# 3_CAN.net
KiCad netlist of a schematic drawn in Altium Designer
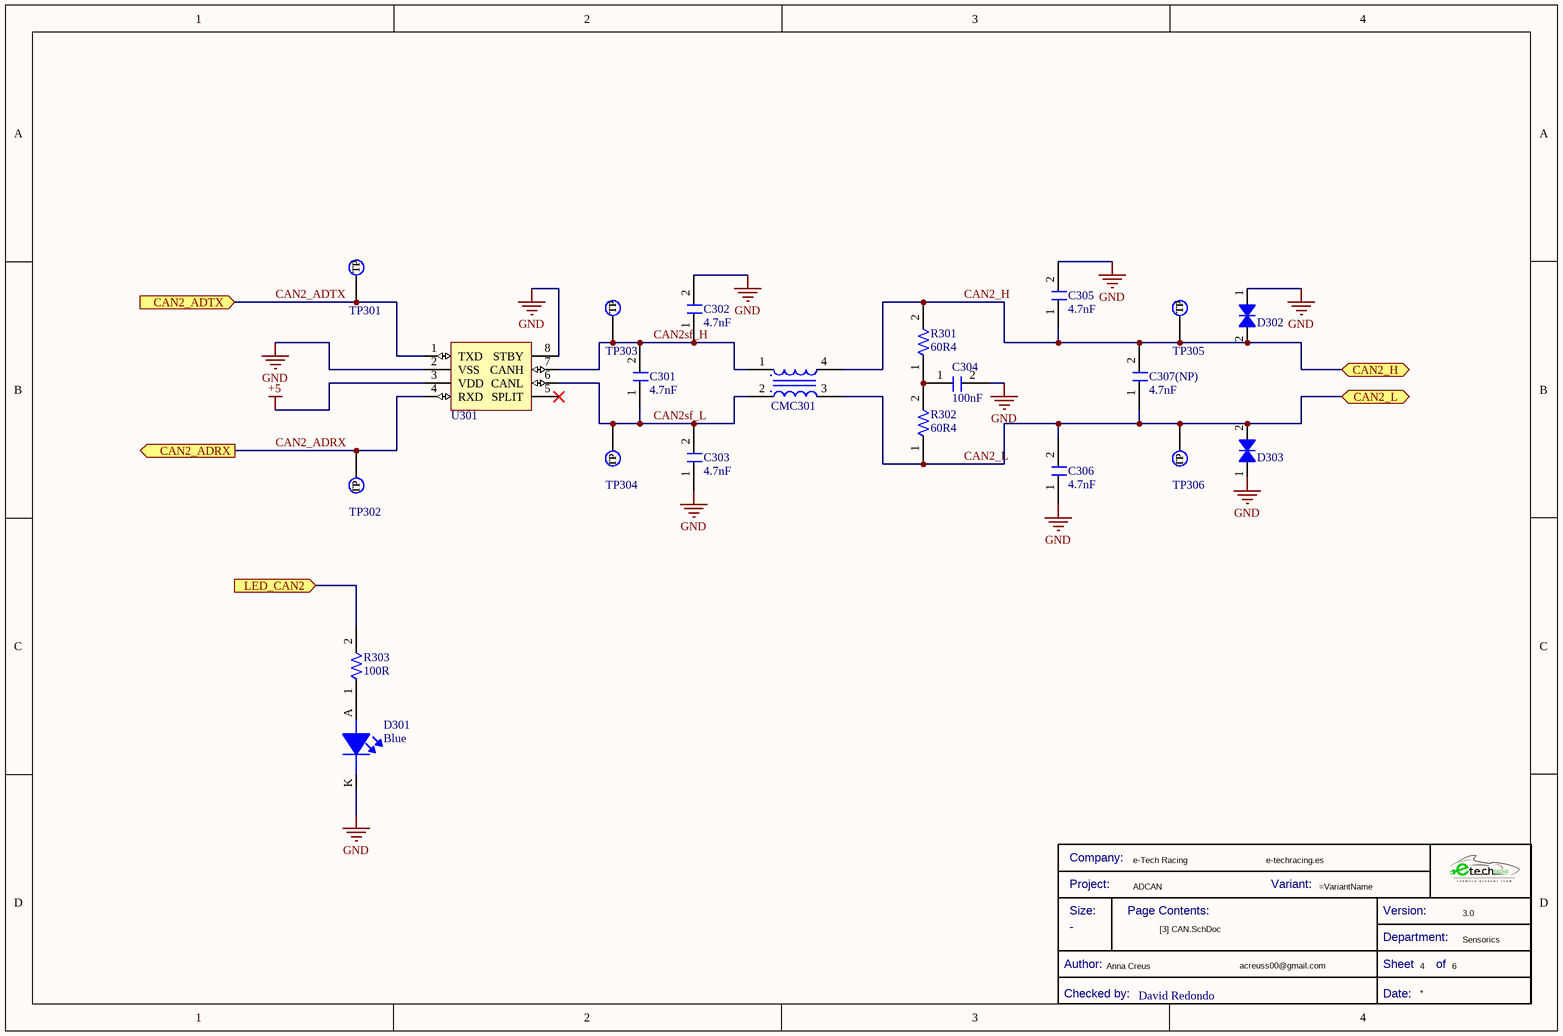
[diagram p0: [3] CAN.SchDoc]

(export (version "E")
  (design (tool "Eeschema 10.0.6"))
  (components
    (comp (ref "C301")
      (value "885012208025")
      (footprint "C1206FNPC-RW")
      (description "Cap, 4700PF, 16V, 10%, X7R, 1206")
      (fields
        (field (name "MANUFACTURER") "Wurth Electronics")
        (field (name "TOLERANCE") "10%")
        (field (name "CAPACITANCE") "4.7nF")
      )
      (libsource (lib "Passives") (part "C4.7n-16V-1206FNPC-X7R"))
    )
    (comp (ref "C302")
      (value "885012208025")
      (footprint "C1206FNPC-RW")
      (description "Cap, 4700PF, 16V, 10%, X7R, 1206")
      (fields
        (field (name "MANUFACTURER") "Wurth Electronics")
        (field (name "TOLERANCE") "10%")
        (field (name "CAPACITANCE") "4.7nF")
      )
      (libsource (lib "Passives") (part "C4.7n-16V-1206FNPC-X7R"))
    )
    (comp (ref "C303")
      (value "885012208025")
      (footprint "C1206FNPC-RW")
      (description "Cap, 4700PF, 16V, 10%, X7R, 1206")
      (fields
        (field (name "MANUFACTURER") "Wurth Electronics")
        (field (name "TOLERANCE") "10%")
        (field (name "CAPACITANCE") "4.7nF")
      )
      (libsource (lib "Passives") (part "C4.7n-16V-1206FNPC-X7R"))
    )
    (comp (ref "C304")
      (value "885012208009")
      (footprint "C1206FNPC-RW")
      (description "Cap, 0.1ΜF, 10V, 10%, X7R, 1206")
      (fields (field (name "TOLERANCE") "10%") (field (name "CAPACITANCE") "100nF"))
      (libsource (lib "Passives") (part "C100n-10V-1206FNPC-X7R"))
    )
    (comp (ref "C305")
      (value "885012208025")
      (footprint "C1206FNPC-RW")
      (description "Cap, 4700PF, 16V, 10%, X7R, 1206")
      (fields
        (field (name "MANUFACTURER") "Wurth Electronics")
        (field (name "TOLERANCE") "10%")
        (field (name "CAPACITANCE") "4.7nF")
      )
      (libsource (lib "Passives") (part "C4.7n-16V-1206FNPC-X7R"))
    )
    (comp (ref "C306")
      (value "885012208025")
      (footprint "C1206FNPC-RW")
      (description "Cap, 4700PF, 16V, 10%, X7R, 1206")
      (fields
        (field (name "MANUFACTURER") "Wurth Electronics")
        (field (name "TOLERANCE") "10%")
        (field (name "CAPACITANCE") "4.7nF")
      )
      (libsource (lib "Passives") (part "C4.7n-16V-1206FNPC-X7R"))
    )
    (comp (ref "C307(NP)")
      (value "885012208025")
      (footprint "C1206FNPC-RW")
      (description "Cap, 4700PF, 16V, 10%, X7R, 1206")
      (fields
        (field (name "MANUFACTURER") "Wurth Electronics")
        (field (name "TOLERANCE") "10%")
        (field (name "CAPACITANCE") "4.7nF")
      )
      (libsource (lib "Passives") (part "C4.7n-16V-1206FNPC-X7R"))
    )
    (comp (ref "CMC301")
      (value "744226")
      (footprint "CMC_10u_1.6A")
      (description "Common Mode Chokes Dual 10uH 920Ohm 1kHz 1.6A 80mOhm DCR SMD T/R")
      (fields (field (name "MANUFACTURER") "Wurth Electronics") (field (name "TOLERANCE") "30%"))
      (libsource (lib "Filter components") (part "CMC_10u_1.6A"))
    )
    (comp (ref "D301")
      (value "150120BS75000")
      (footprint "LED_1206_WE")
      (description "Led, Blue, 470 Nm, 3.2 V, 30 Ma, 145 Mcd Rohs Compliant: Yes")
      (fields (field (name "MANUFACTURER") "Wurth Electronics") (field (name "COLOR") "Blue"))
      (libsource (lib "Semiconductor") (part "LEDBS-1206-145"))
    )
    (comp (ref "D302")
      (value "824501600")
      (footprint "DTVS-DO-214AC")
      (description "TVS diode [Würth Elektronik] 824501600 TVS diode")
      (fields (field (name "MANUFACTURER") "Wurth Electronics"))
      (libsource (lib "Filter components") (part "DTVS-6V-DO-214AC"))
    )
    (comp (ref "D303")
      (value "824501600")
      (footprint "DTVS-DO-214AC")
      (description "TVS diode [Würth Elektronik] 824501600 TVS diode")
      (fields (field (name "MANUFACTURER") "Wurth Electronics"))
      (libsource (lib "Filter components") (part "DTVS-6V-DO-214AC"))
    )
    (comp (ref "R301")
      (value "60R4")
      (footprint "R1206FTK-W")
      (description "Res Precision Thin Film 60.4Ohm 0.1% 400mW 10ppm/°C 2-Pin 1206 SMD T/R")
      (fields
        (field (name "MANUFACTURER") "TE Connectivity Holsworthy")
        (field (name "MANUFACTURER PART NUMBER") "RQ73C2B60R4BTDF")
      )
      (libsource (lib "Passives") (part "R60-1206FTN"))
    )
    (comp (ref "R302")
      (value "60R4")
      (footprint "R1206FTK-W")
      (description "Res Precision Thin Film 60.4Ohm 0.1% 400mW 10ppm/°C 2-Pin 1206 SMD T/R")
      (fields
        (field (name "MANUFACTURER") "TE Connectivity Holsworthy")
        (field (name "MANUFACTURER PART NUMBER") "RQ73C2B60R4BTDF")
      )
      (libsource (lib "Passives") (part "R60-1206FTN"))
    )
    (comp (ref "R303")
      (value "CRG1206F100R")
      (footprint "R1206FTK-W")
      (description "Res Thick Film 1206 100 Ohm 1% 0.25W(1/4W) ±200ppm/C Pad SMD T/R")
      (fields
        (field (name "MANUFACTURER") "TE Connectivity")
        (field (name "TOLERANCE") "1%")
        (field (name "RESISTANCE") "100R")
      )
      (libsource (lib "Passives") (part "R100-1206FTK"))
    )
    (comp (ref "TP301")
      (value "TestPoint")
      (footprint "TestPoint")
      (description "Test Point 1x1 mm")
      (libsource (lib "e-Tech_Racing") (part "TestPoint"))
    )
    (comp (ref "TP302")
      (value "TestPoint")
      (footprint "TestPoint")
      (description "Test Point 1x1 mm")
      (libsource (lib "e-Tech_Racing") (part "TestPoint"))
    )
    (comp (ref "TP303")
      (value "TestPoint")
      (footprint "TestPoint")
      (description "Test Point 1x1 mm")
      (libsource (lib "e-Tech_Racing") (part "TestPoint"))
    )
    (comp (ref "TP304")
      (value "TestPoint")
      (footprint "TestPoint")
      (description "Test Point 1x1 mm")
      (libsource (lib "e-Tech_Racing") (part "TestPoint"))
    )
    (comp (ref "TP305")
      (value "TestPoint")
      (footprint "TestPoint")
      (description "Test Point 1x1 mm")
      (libsource (lib "e-Tech_Racing") (part "TestPoint"))
    )
    (comp (ref "TP306")
      (value "TestPoint")
      (footprint "TestPoint")
      (description "Test Point 1x1 mm")
      (libsource (lib "e-Tech_Racing") (part "TestPoint"))
    )
    (comp (ref "U301")
      (value "MCP2561-H/SN")
      (footprint "Transceiver_CAN")
      (description "CAN Transceiver, 4.5 to 5.5V, 70mA, -40 to 150C, SOIC-8, RoHS")
      (fields (field (name "MANUFACTURER") "Digi-Key") (field (name "MANUFACTURER PART") "Microchip"))
      (libsource (lib "Integrated circuits") (part "Transceiver_CAN"))
    )
  )
  (nets
    (net (code "1") (name "+5") (class "Default")
      (node (ref "U301") (pin "3") (pinfunction "VDD_3") (pintype "power_in"))
    )
    (net (code "2") (name "/CAN2_ADRX") (class "Default")
      (node (ref "TP302") (pin "1") (pinfunction "TP_1") (pintype "passive"))
      (node (ref "U301") (pin "4") (pinfunction "RXD_4") (pintype "bidirectional"))
    )
    (net (code "3") (name "/CAN2_ADTX") (class "Default")
      (node (ref "TP301") (pin "1") (pinfunction "TP_1") (pintype "passive"))
      (node (ref "U301") (pin "1") (pinfunction "TXD_1") (pintype "bidirectional"))
    )
    (net (code "4") (name "/CAN2_H") (class "Default")
      (node (ref "C305") (pin "1") (pinfunction "1_1") (pintype "passive"))
      (node (ref "C307(NP)") (pin "2") (pinfunction "2_2") (pintype "passive"))
      (node (ref "CMC301") (pin "4") (pinfunction "4_OUT_4") (pintype "passive"))
      (node (ref "D302") (pin "2") (pinfunction "2_2") (pintype "passive"))
      (node (ref "R301") (pin "2") (pinfunction "2_2") (pintype "passive"))
      (node (ref "TP305") (pin "1") (pinfunction "TP_1") (pintype "passive"))
    )
    (net (code "5") (name "/CAN2_L") (class "Default")
      (node (ref "C306") (pin "2") (pinfunction "2_2") (pintype "passive"))
      (node (ref "C307(NP)") (pin "1") (pinfunction "1_1") (pintype "passive"))
      (node (ref "CMC301") (pin "3") (pinfunction "3_OUT_3") (pintype "passive"))
      (node (ref "D303") (pin "2") (pinfunction "2_2") (pintype "passive"))
      (node (ref "R302") (pin "1") (pinfunction "1_1") (pintype "passive"))
      (node (ref "TP306") (pin "1") (pinfunction "TP_1") (pintype "passive"))
    )
    (net (code "6") (name "/CAN2sf_H") (class "Default")
      (node (ref "C301") (pin "2") (pinfunction "2_2") (pintype "passive"))
      (node (ref "C302") (pin "1") (pinfunction "1_1") (pintype "passive"))
      (node (ref "CMC301") (pin "1") (pinfunction "1_IN_1") (pintype "passive"))
      (node (ref "TP303") (pin "1") (pinfunction "TP_1") (pintype "passive"))
      (node (ref "U301") (pin "7") (pinfunction "CANH_7") (pintype "bidirectional"))
    )
    (net (code "7") (name "/CAN2sf_L") (class "Default")
      (node (ref "C301") (pin "1") (pinfunction "1_1") (pintype "passive"))
      (node (ref "C303") (pin "2") (pinfunction "2_2") (pintype "passive"))
      (node (ref "CMC301") (pin "2") (pinfunction "2_IN_2") (pintype "passive"))
      (node (ref "TP304") (pin "1") (pinfunction "TP_1") (pintype "passive"))
      (node (ref "U301") (pin "6") (pinfunction "CANL_6") (pintype "bidirectional"))
    )
    (net (code "8") (name "/LED_CAN2") (class "Default")
      (node (ref "R303") (pin "2") (pinfunction "2_2") (pintype "passive"))
    )
    (net (code "9") (name "GND") (class "Default")
      (node (ref "C302") (pin "2") (pinfunction "2_2") (pintype "passive"))
      (node (ref "C303") (pin "1") (pinfunction "1_1") (pintype "passive"))
      (node (ref "C304") (pin "2") (pinfunction "2_2") (pintype "passive"))
      (node (ref "C305") (pin "2") (pinfunction "2_2") (pintype "passive"))
      (node (ref "C306") (pin "1") (pinfunction "1_1") (pintype "passive"))
      (node (ref "D301") (pin "K") (pinfunction "K_K") (pintype "passive"))
      (node (ref "D302") (pin "1") (pinfunction "1_1") (pintype "passive"))
      (node (ref "D303") (pin "1") (pinfunction "1_1") (pintype "passive"))
      (node (ref "U301") (pin "2") (pinfunction "VSS_2") (pintype "power_in"))
      (node (ref "U301") (pin "8") (pinfunction "STBY_8") (pintype "passive"))
    )
    (net (code "10") (name "Net-(C304-Pad1)") (class "Default")
      (node (ref "C304") (pin "1") (pinfunction "1_1") (pintype "passive"))
      (node (ref "R301") (pin "1") (pinfunction "1_1") (pintype "passive"))
      (node (ref "R302") (pin "2") (pinfunction "2_2") (pintype "passive"))
    )
    (net (code "11") (name "Net-(D301-PadA)") (class "Default")
      (node (ref "D301") (pin "A") (pinfunction "A_A") (pintype "passive"))
      (node (ref "R303") (pin "1") (pinfunction "1_1") (pintype "passive"))
    )
    (net (code "12") (name "unconnected-(U301-SPLIT-Pad5)") (class "Default")
      (node (ref "U301") (pin "5") (pinfunction "SPLIT_5") (pintype "passive+no_connect"))
    )
  )
)
